# Atmega32Dip40.net
KiCad netlist of a schematic drawn in EAGLE
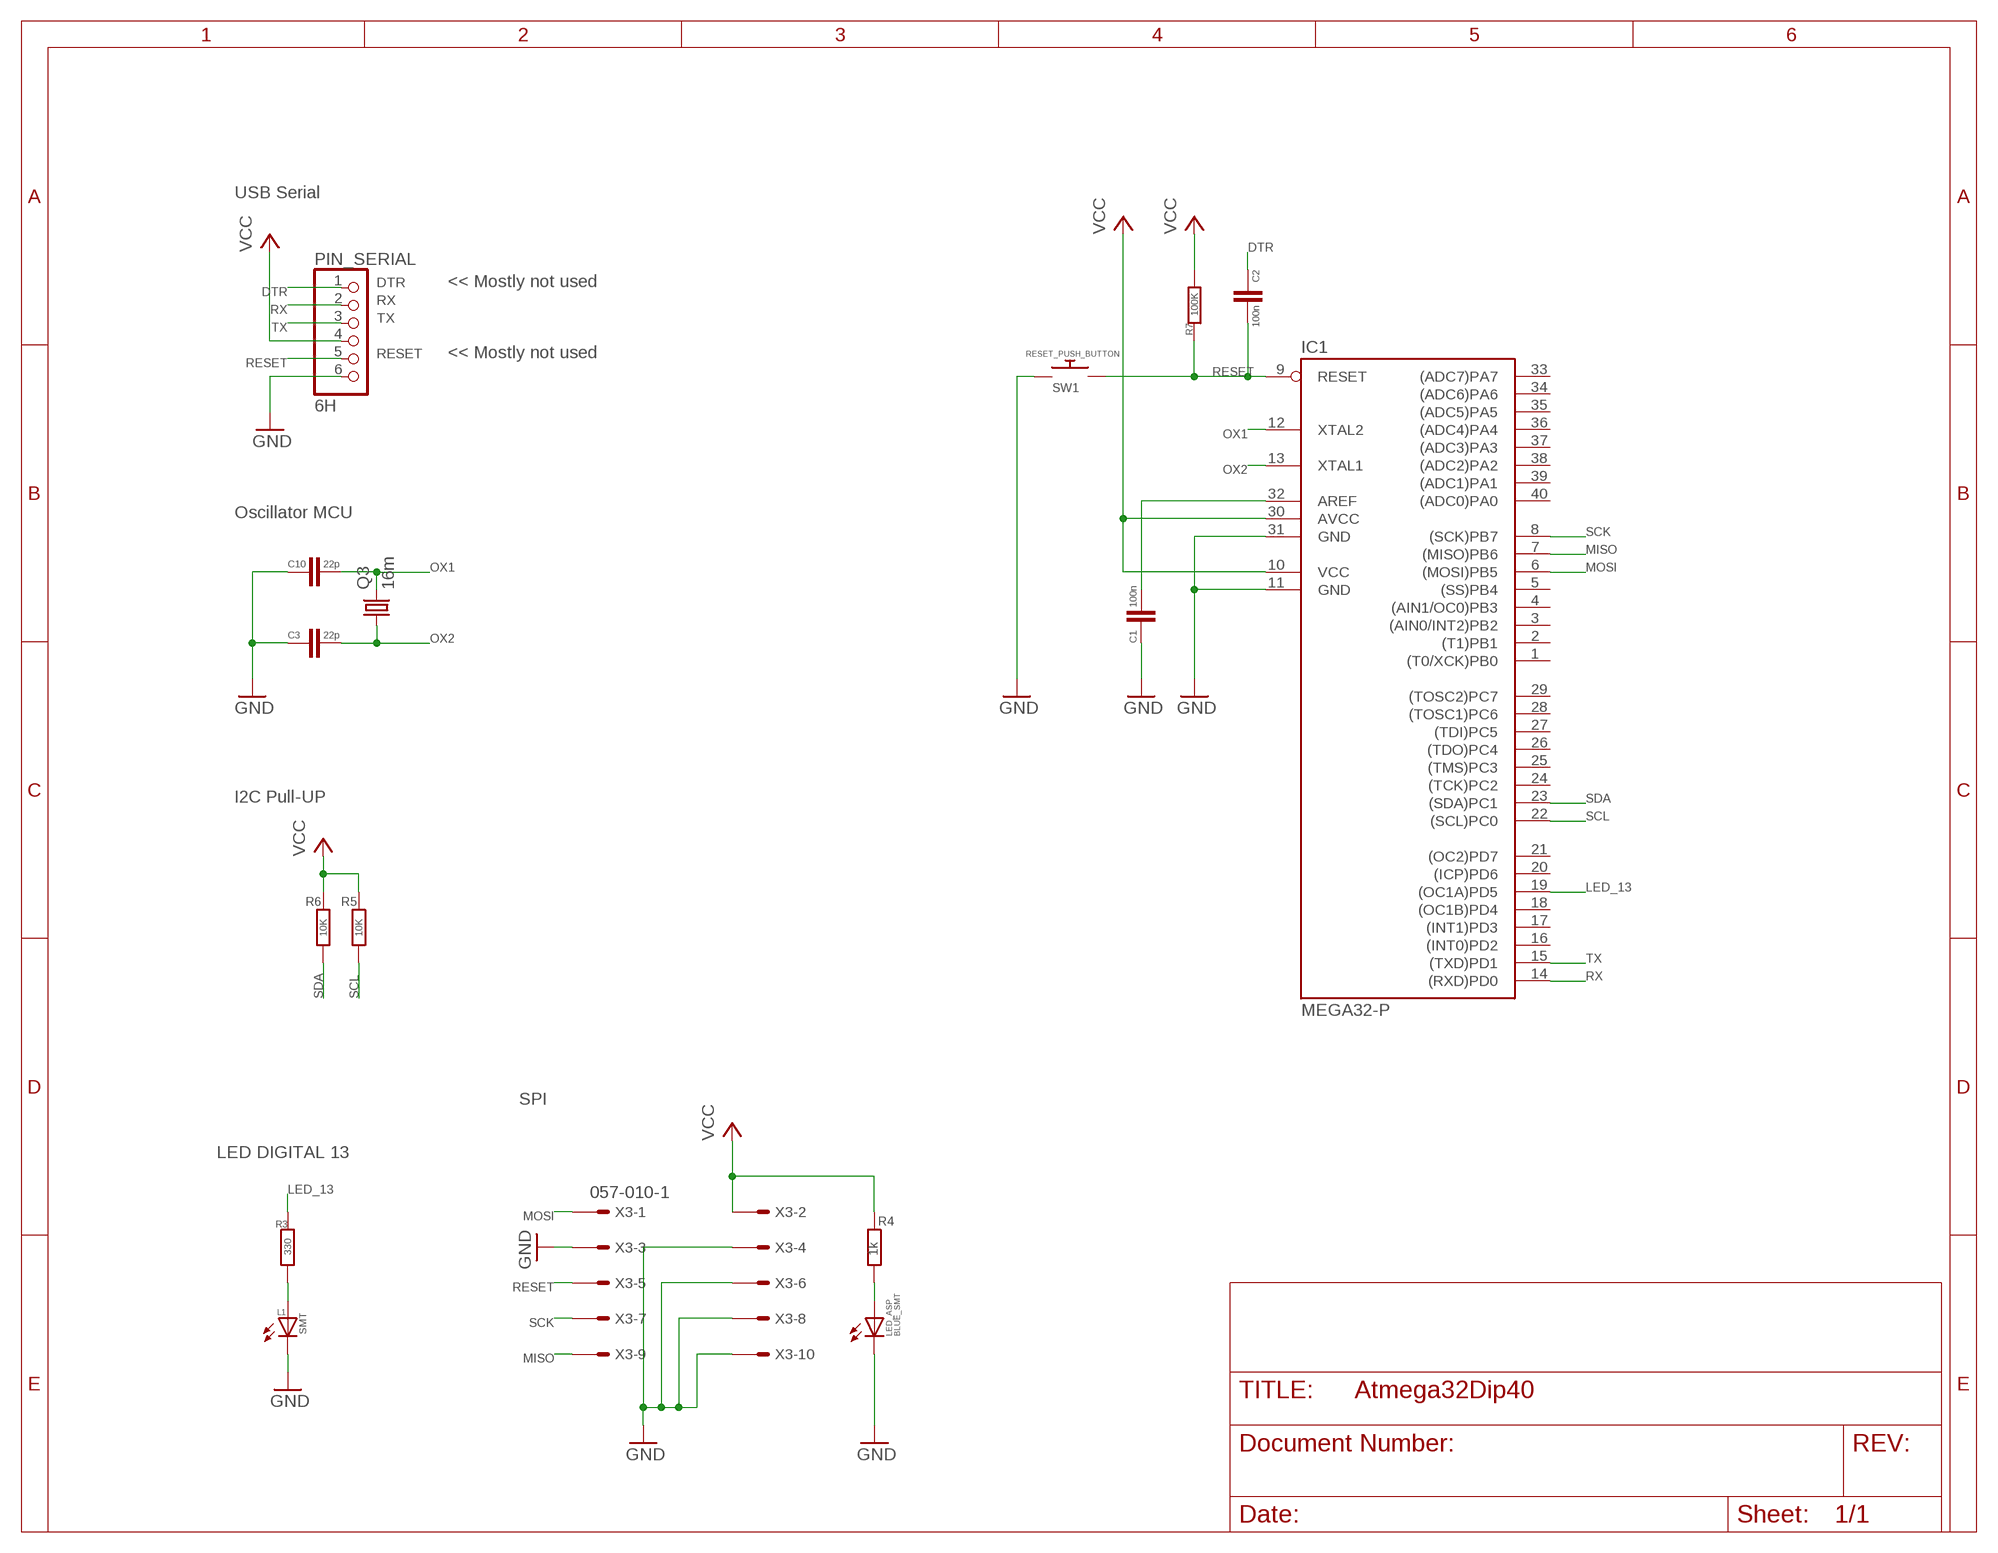
[diagram p0: schematic, sheet 1]

(export (version "E")
  (design (tool "Eeschema 10.0.6"))
  (components
    (comp (ref "C1")
      (value "100n")
      (footprint "eagle-import:C1206")
      (libsource (lib "eagle-import") (part "C-EUC1206"))
    )
    (comp (ref "C2")
      (value "100n")
      (footprint "eagle-import:C1206")
      (libsource (lib "eagle-import") (part "C-EUC1206"))
    )
    (comp (ref "C3")
      (value "22p")
      (footprint "eagle-import:C1206")
      (libsource (lib "eagle-import") (part "C-EUC1206"))
    )
    (comp (ref "C10")
      (value "22p")
      (footprint "eagle-import:C1206")
      (libsource (lib "eagle-import") (part "C-EUC1206"))
    )
    (comp (ref "IC1")
      (value "MEGA32-P")
      (footprint "eagle-import:DIL40")
      (fields (field (name "MPN") "ATMEGA32-16PU"))
      (libsource (lib "eagle-import") (part "MEGA32-P"))
    )
    (comp (ref "L1")
      (value "SMT")
      (footprint "eagle-import:1206")
      (libsource (lib "eagle-import") (part "LEDSMT1206"))
    )
    (comp (ref "LED_ASP")
      (value "BLUE_SMT")
      (footprint "eagle-import:1206")
      (libsource (lib "eagle-import") (part "LEDSMT1206"))
    )
    (comp (ref "PIN_SERIAL")
      (value "6H")
      (footprint "eagle-import:1X06")
      (libsource (lib "eagle-import") (part "PINHD-1X6"))
    )
    (comp (ref "Q3")
      (value "16m")
      (footprint "eagle-import:HC49UP")
      (libsource (lib "eagle-import") (part "CRYSTALHC49UP"))
    )
    (comp (ref "R3")
      (value "330")
      (footprint "eagle-import:R1206")
      (libsource (lib "eagle-import") (part "R-EU_R1206"))
    )
    (comp (ref "R4")
      (value "1k")
      (footprint "eagle-import:R1206")
      (libsource (lib "eagle-import") (part "R-EU_R1206"))
    )
    (comp (ref "R5")
      (value "10K")
      (footprint "eagle-import:0204_7")
      (libsource (lib "eagle-import") (part "R-EU_0204/7"))
    )
    (comp (ref "R6")
      (value "10K")
      (footprint "eagle-import:0204_7")
      (libsource (lib "eagle-import") (part "R-EU_0204/7"))
    )
    (comp (ref "R7")
      (value "100K")
      (footprint "eagle-import:0204_7")
      (libsource (lib "eagle-import") (part "R-EU_0204/7"))
    )
    (comp (ref "RESET_PUSH_BUTTON")
      (value "SW1")
      (footprint "eagle-import:TACT_PANA-EVQ")
      (libsource (lib "eagle-import") (part "SWITCH_PUSHBUTTONEVQ-PE"))
    )
    (comp (ref "X3")
      (value "057-010-1")
      (footprint "eagle-import:057-010-1")
      (libsource (lib "eagle-import") (part "057-010-1"))
    )
  )
  (nets
    (net (code "1") (name "/DTR") (class "Default")
      (node (ref "C2") (pin "1") (pinfunction "1_1") (pintype "passive"))
      (node (ref "PIN_SERIAL") (pin "1") (pinfunction "1_1") (pintype "passive"))
    )
    (net (code "2") (name "/LED_13") (class "Default")
      (node (ref "IC1") (pin "19") (pinfunction "(OC1A)PD5_19") (pintype "bidirectional"))
      (node (ref "R3") (pin "1") (pinfunction "1_1") (pintype "passive"))
    )
    (net (code "3") (name "/MISO") (class "Default")
      (node (ref "IC1") (pin "7") (pinfunction "(MISO)PB6_7") (pintype "bidirectional"))
      (node (ref "X3") (pin "9") (pinfunction "S_9") (pintype "passive"))
    )
    (net (code "4") (name "/MOSI") (class "Default")
      (node (ref "IC1") (pin "6") (pinfunction "(MOSI)PB5_6") (pintype "bidirectional"))
      (node (ref "X3") (pin "1") (pinfunction "S_1") (pintype "passive"))
    )
    (net (code "5") (name "/OX1") (class "Default")
      (node (ref "C10") (pin "2") (pinfunction "2_2") (pintype "passive"))
      (node (ref "IC1") (pin "12") (pinfunction "XTAL2_12") (pintype "bidirectional"))
      (node (ref "Q3") (pin "2") (pinfunction "2_2") (pintype "passive"))
    )
    (net (code "6") (name "/OX2") (class "Default")
      (node (ref "C3") (pin "2") (pinfunction "2_2") (pintype "passive"))
      (node (ref "IC1") (pin "13") (pinfunction "XTAL1_13") (pintype "bidirectional"))
      (node (ref "Q3") (pin "1") (pinfunction "1_1") (pintype "passive"))
    )
    (net (code "7") (name "/RESET") (class "Default")
      (node (ref "C2") (pin "2") (pinfunction "2_2") (pintype "passive"))
      (node (ref "IC1") (pin "9") (pinfunction "RESET_9") (pintype "input"))
      (node (ref "PIN_SERIAL") (pin "5") (pinfunction "5_5") (pintype "passive"))
      (node (ref "R7") (pin "1") (pinfunction "1_1") (pintype "passive"))
      (node (ref "RESET_PUSH_BUTTON") (pin "P$2") (pinfunction "P$2_P$2") (pintype "passive"))
      (node (ref "X3") (pin "5") (pinfunction "S_5") (pintype "passive"))
    )
    (net (code "8") (name "/RX") (class "Default")
      (node (ref "IC1") (pin "14") (pinfunction "(RXD)PD0_14") (pintype "bidirectional"))
      (node (ref "PIN_SERIAL") (pin "2") (pinfunction "2_2") (pintype "passive"))
    )
    (net (code "9") (name "/SCK") (class "Default")
      (node (ref "IC1") (pin "8") (pinfunction "(SCK)PB7_8") (pintype "bidirectional"))
      (node (ref "X3") (pin "7") (pinfunction "S_7") (pintype "passive"))
    )
    (net (code "10") (name "/SCL") (class "Default")
      (node (ref "IC1") (pin "22") (pinfunction "(SCL)PC0_22") (pintype "bidirectional"))
      (node (ref "R5") (pin "2") (pinfunction "2_2") (pintype "passive"))
    )
    (net (code "11") (name "/SDA") (class "Default")
      (node (ref "IC1") (pin "23") (pinfunction "(SDA)PC1_23") (pintype "bidirectional"))
      (node (ref "R6") (pin "2") (pinfunction "2_2") (pintype "passive"))
    )
    (net (code "12") (name "/TX") (class "Default")
      (node (ref "IC1") (pin "15") (pinfunction "(TXD)PD1_15") (pintype "bidirectional"))
      (node (ref "PIN_SERIAL") (pin "3") (pinfunction "3_3") (pintype "passive"))
    )
    (net (code "13") (name "GND") (class "Default")
      (node (ref "C1") (pin "1") (pinfunction "1_1") (pintype "passive"))
      (node (ref "C10") (pin "1") (pinfunction "1_1") (pintype "passive"))
      (node (ref "C3") (pin "1") (pinfunction "1_1") (pintype "passive"))
      (node (ref "IC1") (pin "11") (pinfunction "GND_11") (pintype "power_in"))
      (node (ref "IC1") (pin "31") (pinfunction "GND_31") (pintype "power_in"))
      (node (ref "L1") (pin "C") (pinfunction "C_C") (pintype "passive"))
      (node (ref "LED_ASP") (pin "C") (pinfunction "C_C") (pintype "passive"))
      (node (ref "PIN_SERIAL") (pin "6") (pinfunction "6_6") (pintype "passive"))
      (node (ref "RESET_PUSH_BUTTON") (pin "P$1") (pinfunction "P$1_P$1") (pintype "passive"))
      (node (ref "X3") (pin "10") (pinfunction "S_10") (pintype "passive"))
      (node (ref "X3") (pin "3") (pinfunction "S_3") (pintype "passive"))
      (node (ref "X3") (pin "4") (pinfunction "S_4") (pintype "passive"))
      (node (ref "X3") (pin "6") (pinfunction "S_6") (pintype "passive"))
      (node (ref "X3") (pin "8") (pinfunction "S_8") (pintype "passive"))
    )
    (net (code "14") (name "Net-(IC1-AREF)") (class "Default")
      (node (ref "C1") (pin "2") (pinfunction "2_2") (pintype "passive"))
      (node (ref "IC1") (pin "32") (pinfunction "AREF_32") (pintype "passive"))
    )
    (net (code "15") (name "Net-(L1-PadA)") (class "Default")
      (node (ref "L1") (pin "A") (pinfunction "A_A") (pintype "passive"))
      (node (ref "R3") (pin "2") (pinfunction "2_2") (pintype "passive"))
    )
    (net (code "16") (name "Net-(LED_ASP-PadA)") (class "Default")
      (node (ref "LED_ASP") (pin "A") (pinfunction "A_A") (pintype "passive"))
      (node (ref "R4") (pin "2") (pinfunction "2_2") (pintype "passive"))
    )
    (net (code "17") (name "VCC") (class "Default")
      (node (ref "IC1") (pin "10") (pinfunction "VCC_10") (pintype "power_in"))
      (node (ref "IC1") (pin "30") (pinfunction "AVCC_30") (pintype "power_in"))
      (node (ref "PIN_SERIAL") (pin "4") (pinfunction "4_4") (pintype "passive"))
      (node (ref "R4") (pin "1") (pinfunction "1_1") (pintype "passive"))
      (node (ref "R5") (pin "1") (pinfunction "1_1") (pintype "passive"))
      (node (ref "R6") (pin "1") (pinfunction "1_1") (pintype "passive"))
      (node (ref "R7") (pin "2") (pinfunction "2_2") (pintype "passive"))
      (node (ref "X3") (pin "2") (pinfunction "S_2") (pintype "passive"))
    )
    (net (code "18") (name "unconnected-(IC1-(ADC0)PA0-Pad40)") (class "Default")
      (node (ref "IC1") (pin "40") (pinfunction "(ADC0)PA0_40") (pintype "bidirectional"))
    )
    (net (code "19") (name "unconnected-(IC1-(ADC1)PA1-Pad39)") (class "Default")
      (node (ref "IC1") (pin "39") (pinfunction "(ADC1)PA1_39") (pintype "bidirectional"))
    )
    (net (code "20") (name "unconnected-(IC1-(ADC2)PA2-Pad38)") (class "Default")
      (node (ref "IC1") (pin "38") (pinfunction "(ADC2)PA2_38") (pintype "bidirectional"))
    )
    (net (code "21") (name "unconnected-(IC1-(ADC3)PA3-Pad37)") (class "Default")
      (node (ref "IC1") (pin "37") (pinfunction "(ADC3)PA3_37") (pintype "bidirectional"))
    )
    (net (code "22") (name "unconnected-(IC1-(ADC4)PA4-Pad36)") (class "Default")
      (node (ref "IC1") (pin "36") (pinfunction "(ADC4)PA4_36") (pintype "bidirectional"))
    )
    (net (code "23") (name "unconnected-(IC1-(ADC5)PA5-Pad35)") (class "Default")
      (node (ref "IC1") (pin "35") (pinfunction "(ADC5)PA5_35") (pintype "bidirectional"))
    )
    (net (code "24") (name "unconnected-(IC1-(ADC6)PA6-Pad34)") (class "Default")
      (node (ref "IC1") (pin "34") (pinfunction "(ADC6)PA6_34") (pintype "bidirectional"))
    )
    (net (code "25") (name "unconnected-(IC1-(ADC7)PA7-Pad33)") (class "Default")
      (node (ref "IC1") (pin "33") (pinfunction "(ADC7)PA7_33") (pintype "bidirectional"))
    )
    (net (code "26") (name "unconnected-(IC1-(AIN0{slash}INT2)PB2-Pad3)") (class "Default")
      (node (ref "IC1") (pin "3") (pinfunction "(AIN0/INT2)PB2_3") (pintype "bidirectional"))
    )
    (net (code "27") (name "unconnected-(IC1-(AIN1{slash}OC0)PB3-Pad4)") (class "Default")
      (node (ref "IC1") (pin "4") (pinfunction "(AIN1/OC0)PB3_4") (pintype "bidirectional"))
    )
    (net (code "28") (name "unconnected-(IC1-(ICP)PD6-Pad20)") (class "Default")
      (node (ref "IC1") (pin "20") (pinfunction "(ICP)PD6_20") (pintype "bidirectional"))
    )
    (net (code "29") (name "unconnected-(IC1-(INT0)PD2-Pad16)") (class "Default")
      (node (ref "IC1") (pin "16") (pinfunction "(INT0)PD2_16") (pintype "bidirectional"))
    )
    (net (code "30") (name "unconnected-(IC1-(INT1)PD3-Pad17)") (class "Default")
      (node (ref "IC1") (pin "17") (pinfunction "(INT1)PD3_17") (pintype "bidirectional"))
    )
    (net (code "31") (name "unconnected-(IC1-(OC1B)PD4-Pad18)") (class "Default")
      (node (ref "IC1") (pin "18") (pinfunction "(OC1B)PD4_18") (pintype "bidirectional"))
    )
    (net (code "32") (name "unconnected-(IC1-(OC2)PD7-Pad21)") (class "Default")
      (node (ref "IC1") (pin "21") (pinfunction "(OC2)PD7_21") (pintype "bidirectional"))
    )
    (net (code "33") (name "unconnected-(IC1-(SS)PB4-Pad5)") (class "Default")
      (node (ref "IC1") (pin "5") (pinfunction "(SS)PB4_5") (pintype "bidirectional"))
    )
    (net (code "34") (name "unconnected-(IC1-(T0{slash}XCK)PB0-Pad1)") (class "Default")
      (node (ref "IC1") (pin "1") (pinfunction "(T0/XCK)PB0_1") (pintype "bidirectional"))
    )
    (net (code "35") (name "unconnected-(IC1-(T1)PB1-Pad2)") (class "Default")
      (node (ref "IC1") (pin "2") (pinfunction "(T1)PB1_2") (pintype "bidirectional"))
    )
    (net (code "36") (name "unconnected-(IC1-(TCK)PC2-Pad24)") (class "Default")
      (node (ref "IC1") (pin "24") (pinfunction "(TCK)PC2_24") (pintype "bidirectional"))
    )
    (net (code "37") (name "unconnected-(IC1-(TDI)PC5-Pad27)") (class "Default")
      (node (ref "IC1") (pin "27") (pinfunction "(TDI)PC5_27") (pintype "bidirectional"))
    )
    (net (code "38") (name "unconnected-(IC1-(TDO)PC4-Pad26)") (class "Default")
      (node (ref "IC1") (pin "26") (pinfunction "(TDO)PC4_26") (pintype "bidirectional"))
    )
    (net (code "39") (name "unconnected-(IC1-(TMS)PC3-Pad25)") (class "Default")
      (node (ref "IC1") (pin "25") (pinfunction "(TMS)PC3_25") (pintype "bidirectional"))
    )
    (net (code "40") (name "unconnected-(IC1-(TOSC1)PC6-Pad28)") (class "Default")
      (node (ref "IC1") (pin "28") (pinfunction "(TOSC1)PC6_28") (pintype "bidirectional"))
    )
    (net (code "41") (name "unconnected-(IC1-(TOSC2)PC7-Pad29)") (class "Default")
      (node (ref "IC1") (pin "29") (pinfunction "(TOSC2)PC7_29") (pintype "bidirectional"))
    )
  )
)
